# pc_sensything_v1_5.net
KiCad netlist of a schematic drawn in EAGLE
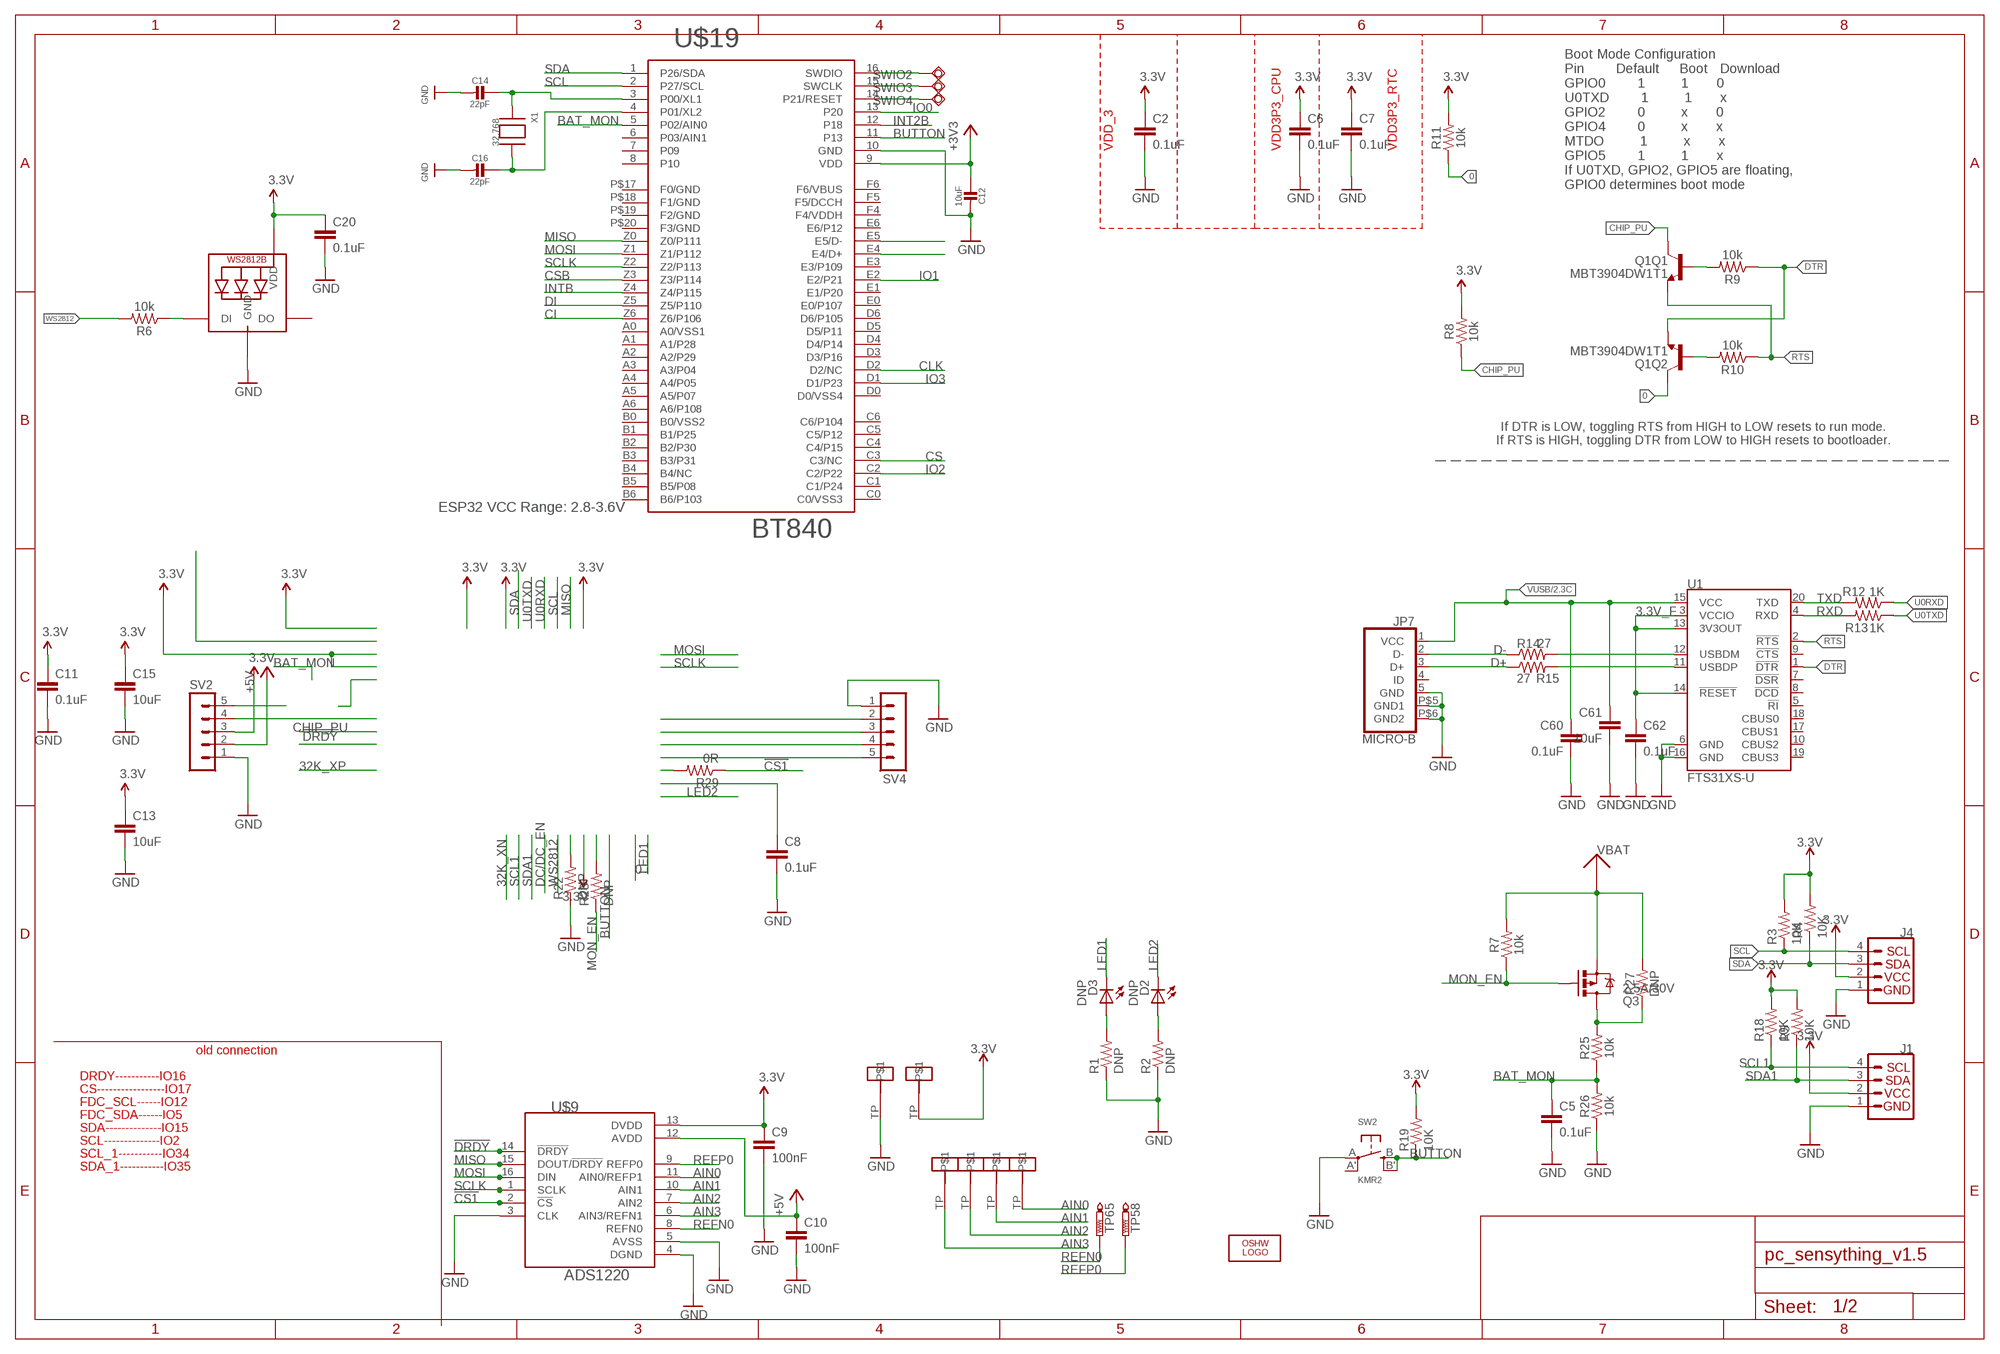
[diagram p0: schematic, sheet 1]
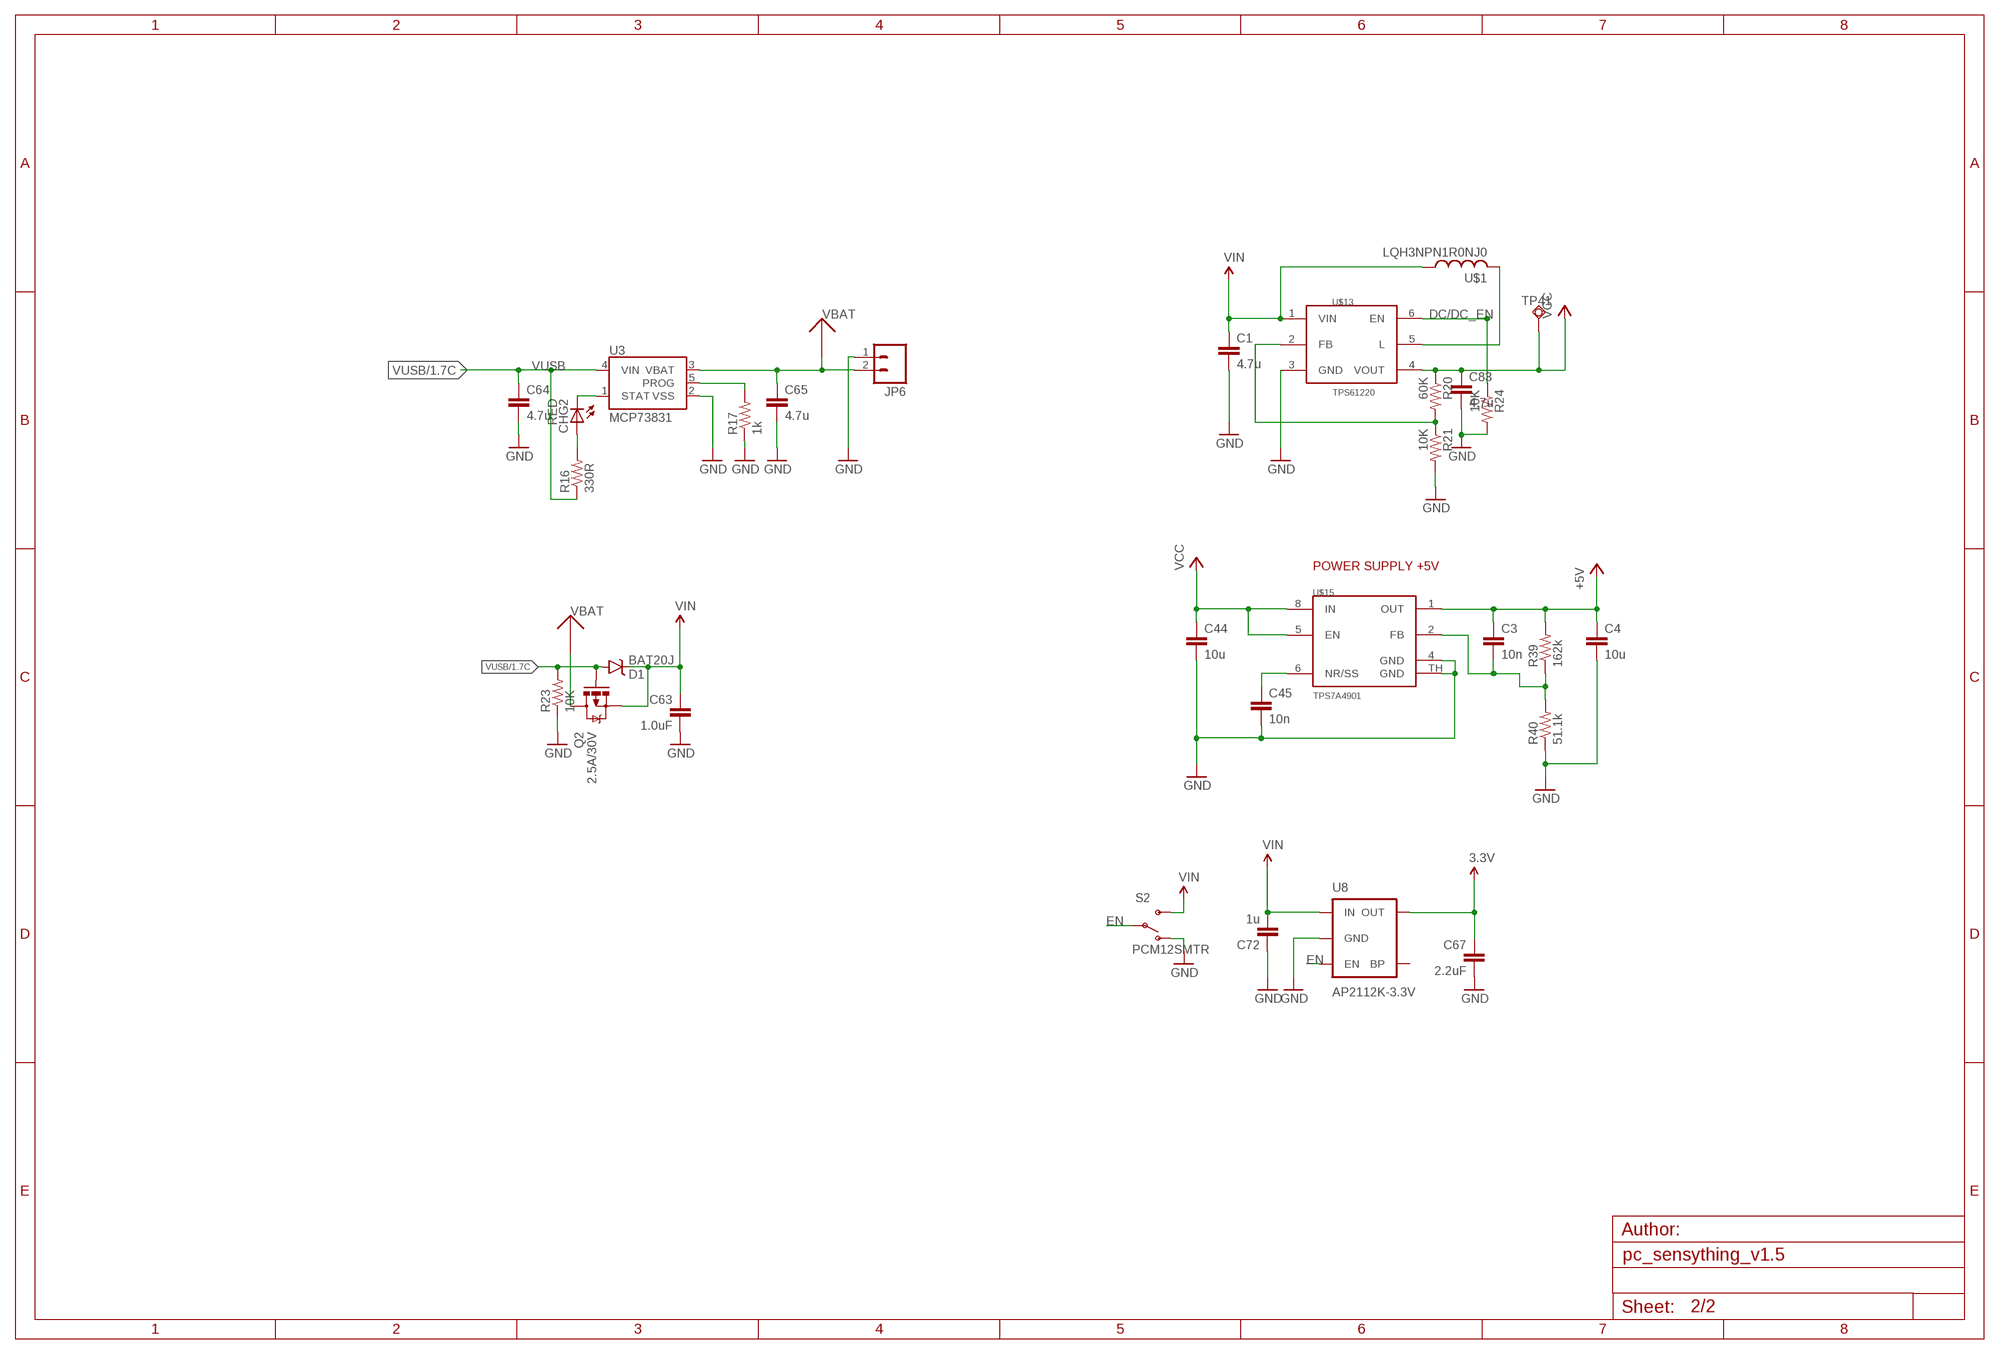
[diagram p1: schematic, sheet 2]

(export (version "E")
  (design (tool "Eeschema 10.0.6"))
  (components
    (comp (ref "C2")
      (value "0.1uF")
      (footprint "eagle-import:0402")
      (libsource (lib "eagle-import") (part "0.1UF-0402-16V-10%"))
    )
    (comp (ref "C5")
      (value "0.1uF")
      (footprint "eagle-import:0402")
      (libsource (lib "eagle-import") (part "0.1UF-0402-16V-10%"))
    )
    (comp (ref "C6")
      (value "0.1uF")
      (footprint "eagle-import:0402")
      (libsource (lib "eagle-import") (part "0.1UF-0402-16V-10%"))
    )
    (comp (ref "C7")
      (value "0.1uF")
      (footprint "eagle-import:0402")
      (libsource (lib "eagle-import") (part "0.1UF-0402-16V-10%"))
    )
    (comp (ref "C8")
      (value "0.1uF")
      (footprint "eagle-import:0402")
      (libsource (lib "eagle-import") (part "0.1UF-0402-16V-10%"))
    )
    (comp (ref "C9")
      (value "100nF")
      (footprint "eagle-import:C0805")
      (libsource (lib "eagle-import") (part "C-EUC0805"))
    )
    (comp (ref "C10")
      (value "100nF")
      (footprint "eagle-import:C0805")
      (libsource (lib "eagle-import") (part "C-EUC0805"))
    )
    (comp (ref "C11")
      (value "0.1uF")
      (footprint "eagle-import:0402")
      (libsource (lib "eagle-import") (part "0.1UF-0402-16V-10%"))
    )
    (comp (ref "C12")
      (value "10uF")
      (footprint "eagle-import:_0402")
      (libsource (lib "eagle-import") (part "CAP_CERAMIC_0402"))
    )
    (comp (ref "C13")
      (value "10uF")
      (footprint "eagle-import:0603")
      (libsource (lib "eagle-import") (part "10UF-0603-6.3V-20%"))
    )
    (comp (ref "C14")
      (value "22pF")
      (footprint "eagle-import:_0402")
      (libsource (lib "eagle-import") (part "CAP_CERAMIC_0402"))
    )
    (comp (ref "C15")
      (value "10uF")
      (footprint "eagle-import:0603")
      (libsource (lib "eagle-import") (part "10UF-0603-6.3V-20%"))
    )
    (comp (ref "C16")
      (value "22pF")
      (footprint "eagle-import:_0402")
      (libsource (lib "eagle-import") (part "CAP_CERAMIC_0402"))
    )
    (comp (ref "C20")
      (value "0.1uF")
      (footprint "eagle-import:0603")
      (libsource (lib "eagle-import") (part "0.1UF-0603-25V-(+80/-20%)"))
    )
    (comp (ref "C60")
      (value "0.1uF")
      (footprint "eagle-import:C0402")
      (libsource (lib "eagle-import") (part "C-EUC0402"))
    )
    (comp (ref "C61")
      (value "10uF")
      (footprint "eagle-import:C0805")
      (libsource (lib "eagle-import") (part "C-EUC0805"))
    )
    (comp (ref "C62")
      (value "0.1uF")
      (footprint "eagle-import:C0402")
      (libsource (lib "eagle-import") (part "C-EUC0402"))
    )
    (comp (ref "D2")
      (value "DNP")
      (footprint "eagle-import:CHIPLED_0603")
      (libsource (lib "eagle-import") (part "LEDCHIPLED_0603"))
    )
    (comp (ref "D3")
      (value "DNP")
      (footprint "eagle-import:CHIPLED_0603")
      (libsource (lib "eagle-import") (part "LEDCHIPLED_0603"))
    )
    (comp (ref "J1")
      (value "QWIIC_CONNECTORJS-1MM")
      (footprint "eagle-import:1X04_1MM_RA")
      (libsource (lib "eagle-import") (part "QWIIC_CONNECTORJS-1MM"))
    )
    (comp (ref "J4")
      (value "QWIIC_CONNECTORJS-1MM")
      (footprint "eagle-import:1X04_1MM_RA")
      (libsource (lib "eagle-import") (part "QWIIC_CONNECTORJS-1MM"))
    )
    (comp (ref "JP7")
      (value "MICRO-B")
      (footprint "eagle-import:MICRO-B")
      (libsource (lib "eagle-import") (part "MICRO-B"))
    )
    (comp (ref "LED1")
      (value "WS2812B5050")
      (footprint "eagle-import:WS2812B")
      (libsource (lib "eagle-import") (part "WS2812B5050"))
    )
    (comp (ref "LOGO3")
      (value "OSHW_LOGO_FILLX0200-NT")
      (footprint "eagle-import:OSHW_FILLX200_NOTEXT")
      (libsource (lib "eagle-import") (part "OSHW_LOGO_FILLX0200-NT"))
    )
    (comp (ref "Q1")
      (value "MBT3904DW1T1")
      (footprint "eagle-import:SC70-6")
      (libsource (lib "eagle-import") (part "MBT3904DW1T1"))
    )
    (comp (ref "Q3")
      (value "2.5A/30V")
      (footprint "eagle-import:SOT23-3")
      (libsource (lib "eagle-import") (part "MOSFET-PCHANNELDMG2307L"))
    )
    (comp (ref "R1")
      (value "DNP")
      (footprint "eagle-import:R0402")
      (libsource (lib "eagle-import") (part "R-US_R0402"))
    )
    (comp (ref "R2")
      (value "DNP")
      (footprint "eagle-import:R0402")
      (libsource (lib "eagle-import") (part "R-US_R0402"))
    )
    (comp (ref "R3")
      (value "10K")
      (footprint "eagle-import:R0402")
      (libsource (lib "eagle-import") (part "R-US_R0402"))
    )
    (comp (ref "R4")
      (value "10K")
      (footprint "eagle-import:R0402")
      (libsource (lib "eagle-import") (part "R-US_R0402"))
    )
    (comp (ref "R5")
      (value "10K")
      (footprint "eagle-import:R0402")
      (libsource (lib "eagle-import") (part "R-US_R0402"))
    )
    (comp (ref "R6")
      (value "10k")
      (footprint "eagle-import:0603")
      (libsource (lib "eagle-import") (part "10KOHM-1/10W-1%(0603)0603"))
    )
    (comp (ref "R7")
      (value "10k")
      (footprint "eagle-import:0603")
      (libsource (lib "eagle-import") (part "10KOHM-1/10W-1%(0603)0603"))
    )
    (comp (ref "R8")
      (value "10k")
      (footprint "eagle-import:0603")
      (libsource (lib "eagle-import") (part "10KOHM-1/10W-1%(0603)0603"))
    )
    (comp (ref "R9")
      (value "10k")
      (footprint "eagle-import:0603")
      (libsource (lib "eagle-import") (part "10KOHM-0603-1/10W-1%"))
    )
    (comp (ref "R10")
      (value "10k")
      (footprint "eagle-import:0603")
      (libsource (lib "eagle-import") (part "10KOHM-0603-1/10W-1%"))
    )
    (comp (ref "R11")
      (value "10k")
      (footprint "eagle-import:0603")
      (libsource (lib "eagle-import") (part "10KOHM-1/10W-1%(0603)0603"))
    )
    (comp (ref "R12")
      (value "1K")
      (footprint "eagle-import:R0402")
      (libsource (lib "eagle-import") (part "R-US_R0402"))
    )
    (comp (ref "R13")
      (value "1K")
      (footprint "eagle-import:R0402")
      (libsource (lib "eagle-import") (part "R-US_R0402"))
    )
    (comp (ref "R14")
      (value "27")
      (footprint "eagle-import:R0402")
      (libsource (lib "eagle-import") (part "R-US_R0402"))
    )
    (comp (ref "R15")
      (value "27")
      (footprint "eagle-import:R0402")
      (libsource (lib "eagle-import") (part "R-US_R0402"))
    )
    (comp (ref "R18")
      (value "10K")
      (footprint "eagle-import:R0402")
      (libsource (lib "eagle-import") (part "R-US_R0402"))
    )
    (comp (ref "R19")
      (value "10K")
      (footprint "eagle-import:R0402")
      (libsource (lib "eagle-import") (part "R-US_R0402"))
    )
    (comp (ref "R22")
      (value "DNP")
      (footprint "eagle-import:R0402")
      (libsource (lib "eagle-import") (part "R-US_R0402"))
    )
    (comp (ref "R25")
      (value "10k")
      (footprint "eagle-import:0603")
      (libsource (lib "eagle-import") (part "10KOHM-1/10W-1%(0603)0603"))
    )
    (comp (ref "R26")
      (value "10k")
      (footprint "eagle-import:0603")
      (libsource (lib "eagle-import") (part "10KOHM-1/10W-1%(0603)0603"))
    )
    (comp (ref "R27")
      (value "DNP")
      (footprint "eagle-import:0603")
      (libsource (lib "eagle-import") (part "10KOHM-1/10W-1%(0603)0603"))
    )
    (comp (ref "R28")
      (value "DNP")
      (footprint "eagle-import:R0402")
      (libsource (lib "eagle-import") (part "R-US_R0402"))
    )
    (comp (ref "R29")
      (value "0R")
      (footprint "eagle-import:R0402")
      (libsource (lib "eagle-import") (part "R-US_R0402"))
    )
    (comp (ref "SV2")
      (value "MA05-1")
      (footprint "eagle-import:MA05-1")
      (libsource (lib "eagle-import") (part "MA05-1"))
    )
    (comp (ref "SV4")
      (value "MA05-1")
      (footprint "eagle-import:MA05-1")
      (libsource (lib "eagle-import") (part "MA05-1"))
    )
    (comp (ref "SW2")
      (value "KMR2")
      (footprint "eagle-import:BTN_KMR2_4.6X2.8")
      (libsource (lib "eagle-import") (part "SWITCH_TACT_SMT4.6X2.8"))
    )
    (comp (ref "SWIO2")
      (value "TPSQTP11R")
      (footprint "eagle-import:TP11R")
      (libsource (lib "eagle-import") (part "TPSQTP11R"))
    )
    (comp (ref "SWIO3")
      (value "TPSQTP11R")
      (footprint "eagle-import:TP11R")
      (libsource (lib "eagle-import") (part "TPSQTP11R"))
    )
    (comp (ref "SWIO4")
      (value "TPSQTP11R")
      (footprint "eagle-import:TP11R")
      (libsource (lib "eagle-import") (part "TPSQTP11R"))
    )
    (comp (ref "TP58")
      (value "PTR1PAD1-13")
      (footprint "eagle-import:P1-13")
      (libsource (lib "eagle-import") (part "PTR1PAD1-13"))
    )
    (comp (ref "TP65")
      (value "PTR1PAD1-13")
      (footprint "eagle-import:P1-13")
      (libsource (lib "eagle-import") (part "PTR1PAD1-13"))
    )
    (comp (ref "U$3")
      (value "SENSYTHING_CON")
      (footprint "eagle-import:SENSYTHING_CON")
      (libsource (lib "eagle-import") (part "SENSYTHING_CON"))
    )
    (comp (ref "U$7")
      (value "SENSYTHING_CON")
      (footprint "eagle-import:SENSYTHING_CON")
      (libsource (lib "eagle-import") (part "SENSYTHING_CON"))
    )
    (comp (ref "U$8")
      (value "SENSYTHING_CON")
      (footprint "eagle-import:SENSYTHING_CON")
      (libsource (lib "eagle-import") (part "SENSYTHING_CON"))
    )
    (comp (ref "U$9")
      (value "ADS1220")
      (footprint "eagle-import:TSSOP-16")
      (libsource (lib "eagle-import") (part "ADS1220"))
    )
    (comp (ref "U$11")
      (value "SENSYTHING_CON")
      (footprint "eagle-import:SENSYTHING_CON")
      (libsource (lib "eagle-import") (part "SENSYTHING_CON"))
    )
    (comp (ref "U$12")
      (value "SENSYTHING_CON")
      (footprint "eagle-import:SENSYTHING_CON")
      (libsource (lib "eagle-import") (part "SENSYTHING_CON"))
    )
    (comp (ref "U$14")
      (value "SENSYTHING_CON")
      (footprint "eagle-import:SENSYTHING_CON")
      (libsource (lib "eagle-import") (part "SENSYTHING_CON"))
    )
    (comp (ref "U$19")
      (value "BT840")
      (footprint "eagle-import:BT840")
      (libsource (lib "eagle-import") (part "BT840"))
    )
    (comp (ref "U1")
      (value "FTS31XS-U")
      (footprint "eagle-import:SSOP20_L")
      (libsource (lib "eagle-import") (part "FT231XS"))
    )
    (comp (ref "X1")
      (value "32.768")
      (footprint "eagle-import:XTAL3215")
      (libsource (lib "eagle-import") (part "XTAL-3.2X1.5"))
    )
    (comp (ref "C1")
      (value "4.7u")
      (footprint "eagle-import:C0805")
      (libsource (lib "eagle-import") (part "C-EUC0805"))
    )
    (comp (ref "C3")
      (value "10n")
      (footprint "eagle-import:C0402")
      (libsource (lib "eagle-import") (part "C-EUC0402"))
    )
    (comp (ref "C4")
      (value "10u")
      (footprint "eagle-import:C0805")
      (libsource (lib "eagle-import") (part "C-EUC0805"))
    )
    (comp (ref "C44")
      (value "10u")
      (footprint "eagle-import:C0805")
      (libsource (lib "eagle-import") (part "C-EUC0805"))
    )
    (comp (ref "C45")
      (value "10n")
      (footprint "eagle-import:C0402")
      (libsource (lib "eagle-import") (part "C-EUC0402"))
    )
    (comp (ref "C63")
      (value "1.0uF")
      (footprint "eagle-import:C0402")
      (libsource (lib "eagle-import") (part "C-EUC0402"))
    )
    (comp (ref "C64")
      (value "4.7u")
      (footprint "eagle-import:C0805")
      (libsource (lib "eagle-import") (part "C-EUC0805"))
    )
    (comp (ref "C65")
      (value "4.7u")
      (footprint "eagle-import:C0805")
      (libsource (lib "eagle-import") (part "C-EUC0805"))
    )
    (comp (ref "C67")
      (value "2.2uF")
      (footprint "eagle-import:C0402")
      (libsource (lib "eagle-import") (part "C-EUC0402"))
    )
    (comp (ref "C72")
      (value "1u")
      (footprint "eagle-import:C0402")
      (libsource (lib "eagle-import") (part "C-EUC0402"))
    )
    (comp (ref "C83")
      (value "4.7u")
      (footprint "eagle-import:C0805")
      (libsource (lib "eagle-import") (part "C-EUC0805"))
    )
    (comp (ref "CHG2")
      (value "RED")
      (footprint "eagle-import:CHIPLED_0603")
      (libsource (lib "eagle-import") (part "LEDCHIPLED_0603"))
    )
    (comp (ref "D1")
      (value "BAT20J")
      (footprint "eagle-import:SOD-323")
      (libsource (lib "eagle-import") (part "DIODE-SCHOTTKY-BAT20J"))
    )
    (comp (ref "JP6")
      (value "M02-JST-2MM-SMT")
      (footprint "eagle-import:JST-2-SMD")
      (libsource (lib "eagle-import") (part "M02-JST-2MM-SMT"))
    )
    (comp (ref "Q2")
      (value "2.5A/30V")
      (footprint "eagle-import:SOT23-3")
      (libsource (lib "eagle-import") (part "MOSFET-PCHANNELDMG2307L"))
    )
    (comp (ref "R16")
      (value "330R")
      (footprint "eagle-import:R0402")
      (libsource (lib "eagle-import") (part "R-US_R0402"))
    )
    (comp (ref "R17")
      (value "1k")
      (footprint "eagle-import:R0402")
      (libsource (lib "eagle-import") (part "R-US_R0402"))
    )
    (comp (ref "R20")
      (value "60K")
      (footprint "eagle-import:R0805")
      (libsource (lib "eagle-import") (part "R-US_R0805"))
    )
    (comp (ref "R21")
      (value "10K")
      (footprint "eagle-import:R0805")
      (libsource (lib "eagle-import") (part "R-US_R0805"))
    )
    (comp (ref "R23")
      (value "10K")
      (footprint "eagle-import:R0402")
      (libsource (lib "eagle-import") (part "R-US_R0402"))
    )
    (comp (ref "R24")
      (value "10K")
      (footprint "eagle-import:R0402")
      (libsource (lib "eagle-import") (part "R-US_R0402"))
    )
    (comp (ref "R39")
      (value "162k")
      (footprint "eagle-import:R0805")
      (libsource (lib "eagle-import") (part "R-US_R0805"))
    )
    (comp (ref "R40")
      (value "51.1k")
      (footprint "eagle-import:R0805")
      (libsource (lib "eagle-import") (part "R-US_R0805"))
    )
    (comp (ref "S2")
      (value "PCM12SMTR")
      (footprint "eagle-import:SWITCH-SPST-SMD-A")
      (libsource (lib "eagle-import") (part "SWITCH-SPDT-SMD-A"))
    )
    (comp (ref "TP41")
      (value "TPSQB1,27")
      (footprint "eagle-import:B1,27")
      (libsource (lib "eagle-import") (part "TPSQB1,27"))
    )
    (comp (ref "U$1")
      (value "LQH3NPN1R0NJ0")
      (footprint "eagle-import:LQH3NP")
      (libsource (lib "eagle-import") (part "LQH3NPN1R0NJ0"))
    )
    (comp (ref "U$13")
      (value "TPS61220")
      (footprint "eagle-import:SC-70-6")
      (libsource (lib "eagle-import") (part "TPS61222"))
    )
    (comp (ref "U$15")
      (value "TPS7A4901")
      (footprint "eagle-import:S-PDSO-G08")
      (libsource (lib "eagle-import") (part "TPS7A4901"))
    )
    (comp (ref "U3")
      (value "MCP73831")
      (footprint "eagle-import:SOT23-5")
      (libsource (lib "eagle-import") (part "MCP73831"))
    )
    (comp (ref "U8")
      (value "AP2112K-3.3V")
      (footprint "eagle-import:SOT23-5")
      (libsource (lib "eagle-import") (part "V_REG_LDOSMD"))
    )
  )
  (nets
    (net (code "1") (name "+3V3") (class "Default")
      (node (ref "C12") (pin "1") (pinfunction "1_1") (pintype "passive"))
      (node (ref "U$19") (pin "9") (pinfunction "VDD_9") (pintype "bidirectional"))
    )
    (net (code "2") (name "+5V") (class "Default")
      (node (ref "C10") (pin "1") (pinfunction "1_1") (pintype "passive"))
      (node (ref "C3") (pin "1") (pinfunction "1_1") (pintype "passive"))
      (node (ref "C4") (pin "1") (pinfunction "1_1") (pintype "passive"))
      (node (ref "R39") (pin "2") (pinfunction "2_2") (pintype "passive"))
      (node (ref "SV2") (pin "2") (pinfunction "2_2") (pintype "passive"))
      (node (ref "U$15") (pin "1") (pinfunction "OUT_1") (pintype "bidirectional"))
      (node (ref "U$9") (pin "12") (pinfunction "AVDD_12") (pintype "bidirectional"))
    )
    (net (code "3") (name "0") (class "Default")
      (node (ref "Q1") (pin "6") (pinfunction "C_6") (pintype "passive"))
      (node (ref "R11") (pin "1") (pinfunction "1_1") (pintype "passive"))
    )
    (net (code "4") (name "3.3V") (class "Default")
      (node (ref "C11") (pin "1") (pinfunction "1_1") (pintype "passive"))
      (node (ref "C13") (pin "1") (pinfunction "1_1") (pintype "passive"))
      (node (ref "C15") (pin "1") (pinfunction "1_1") (pintype "passive"))
      (node (ref "C2") (pin "1") (pinfunction "1_1") (pintype "passive"))
      (node (ref "C20") (pin "1") (pinfunction "1_1") (pintype "passive"))
      (node (ref "C6") (pin "1") (pinfunction "1_1") (pintype "passive"))
      (node (ref "C67") (pin "1") (pinfunction "1_1") (pintype "passive"))
      (node (ref "C7") (pin "1") (pinfunction "1_1") (pintype "passive"))
      (node (ref "C9") (pin "1") (pinfunction "1_1") (pintype "passive"))
      (node (ref "J1") (pin "2") (pinfunction "2_2") (pintype "power_in"))
      (node (ref "J4") (pin "2") (pinfunction "2_2") (pintype "power_in"))
      (node (ref "LED1") (pin "1-VDD") (pinfunction "VDD_1-VDD") (pintype "power_in"))
      (node (ref "R11") (pin "2") (pinfunction "2_2") (pintype "passive"))
      (node (ref "R18") (pin "2") (pinfunction "2_2") (pintype "passive"))
      (node (ref "R19") (pin "2") (pinfunction "2_2") (pintype "passive"))
      (node (ref "R3") (pin "2") (pinfunction "2_2") (pintype "passive"))
      (node (ref "R4") (pin "2") (pinfunction "2_2") (pintype "passive"))
      (node (ref "R5") (pin "2") (pinfunction "2_2") (pintype "passive"))
      (node (ref "R8") (pin "2") (pinfunction "2_2") (pintype "passive"))
      (node (ref "SV2") (pin "3") (pinfunction "3_3") (pintype "passive"))
      (node (ref "U$14") (pin "TP") (pinfunction "P$1_TP") (pintype "bidirectional"))
      (node (ref "U$9") (pin "13") (pinfunction "DVDD_13") (pintype "bidirectional"))
      (node (ref "U8") (pin "5") (pinfunction "OUT_5") (pintype "passive"))
    )
    (net (code "5") (name "3.3V_F") (class "Default")
      (node (ref "C62") (pin "1") (pinfunction "1_1") (pintype "passive"))
      (node (ref "U1") (pin "13") (pinfunction "3V3OUT_13") (pintype "bidirectional"))
      (node (ref "U1") (pin "14") (pinfunction "~{RESET}_14") (pintype "bidirectional"))
      (node (ref "U1") (pin "3") (pinfunction "VCCIO_3") (pintype "bidirectional"))
    )
    (net (code "8") (name "AIN0") (class "Default")
      (node (ref "U$11") (pin "TP") (pinfunction "P$1_TP") (pintype "bidirectional"))
      (node (ref "U$9") (pin "11") (pinfunction "AIN0/REFP1_11") (pintype "bidirectional"))
    )
    (net (code "9") (name "AIN1") (class "Default")
      (node (ref "U$8") (pin "TP") (pinfunction "P$1_TP") (pintype "bidirectional"))
      (node (ref "U$9") (pin "10") (pinfunction "AIN1_10") (pintype "bidirectional"))
    )
    (net (code "10") (name "AIN2") (class "Default")
      (node (ref "U$7") (pin "TP") (pinfunction "P$1_TP") (pintype "bidirectional"))
      (node (ref "U$9") (pin "7") (pinfunction "AIN2_7") (pintype "bidirectional"))
    )
    (net (code "11") (name "AIN3") (class "Default")
      (node (ref "U$3") (pin "TP") (pinfunction "P$1_TP") (pintype "bidirectional"))
      (node (ref "U$9") (pin "6") (pinfunction "AIN3/REFN1_6") (pintype "bidirectional"))
    )
    (net (code "12") (name "BAT_MON") (class "Default")
      (node (ref "C5") (pin "1") (pinfunction "1_1") (pintype "passive"))
      (node (ref "R25") (pin "1") (pinfunction "1_1") (pintype "passive"))
      (node (ref "R26") (pin "2") (pinfunction "2_2") (pintype "passive"))
      (node (ref "U$19") (pin "5") (pinfunction "P02/AIN0_5") (pintype "bidirectional"))
    )
    (net (code "13") (name "BUTTON") (class "Default")
      (node (ref "R19") (pin "1") (pinfunction "1_1") (pintype "passive"))
      (node (ref "SW2") (pin "B") (pinfunction "S_B") (pintype "passive"))
      (node (ref "SW2") (pin "B'") (pinfunction "S1_B'") (pintype "passive"))
      (node (ref "U$19") (pin "11") (pinfunction "P13_11") (pintype "bidirectional"))
    )
    (net (code "14") (name "CHIP_PU") (class "Default")
      (node (ref "Q1") (pin "3") (pinfunction "C_3") (pintype "passive"))
      (node (ref "R8") (pin "1") (pinfunction "1_1") (pintype "passive"))
    )
    (net (code "15") (name "CI") (class "Default")
      (node (ref "U$19") (pin "Z6") (pinfunction "Z6/P106_Z6") (pintype "bidirectional"))
    )
    (net (code "16") (name "CLK") (class "Default")
      (node (ref "U$19") (pin "D2") (pinfunction "D2/NC_D2") (pintype "bidirectional"))
    )
    (net (code "17") (name "CS") (class "Default")
      (node (ref "U$19") (pin "C3") (pinfunction "C3/NC_C3") (pintype "bidirectional"))
    )
    (net (code "18") (name "CSB") (class "Default")
      (node (ref "U$19") (pin "Z3") (pinfunction "Z3/P114_Z3") (pintype "bidirectional"))
    )
    (net (code "19") (name "D+") (class "Default")
      (node (ref "JP7") (pin "3") (pinfunction "D+_3") (pintype "bidirectional"))
      (node (ref "R15") (pin "1") (pinfunction "1_1") (pintype "passive"))
    )
    (net (code "20") (name "D-") (class "Default")
      (node (ref "JP7") (pin "2") (pinfunction "D-_2") (pintype "bidirectional"))
      (node (ref "R14") (pin "1") (pinfunction "1_1") (pintype "passive"))
    )
    (net (code "21") (name "DC{slash}DC_EN") (class "Default")
      (node (ref "R24") (pin "1") (pinfunction "1_1") (pintype "passive"))
      (node (ref "U$13") (pin "6") (pinfunction "EN_6") (pintype "bidirectional"))
    )
    (net (code "22") (name "DI") (class "Default")
      (node (ref "U$19") (pin "Z5") (pinfunction "Z5/P110_Z5") (pintype "bidirectional"))
    )
    (net (code "23") (name "DTR") (class "Default")
      (node (ref "Q1") (pin "1") (pinfunction "E_1") (pintype "passive"))
      (node (ref "R9") (pin "1") (pinfunction "1_1") (pintype "passive"))
      (node (ref "U1") (pin "1") (pinfunction "~{DTR}_1") (pintype "bidirectional"))
    )
    (net (code "24") (name "EN") (class "Default")
      (node (ref "S2") (pin "2") (pinfunction "P_2") (pintype "passive"))
      (node (ref "U8") (pin "3") (pinfunction "EN_3") (pintype "input"))
    )
    (net (code "25") (name "GND") (class "Default")
      (node (ref "C1") (pin "2") (pinfunction "2_2") (pintype "passive"))
      (node (ref "C10") (pin "2") (pinfunction "2_2") (pintype "passive"))
      (node (ref "C11") (pin "2") (pinfunction "2_2") (pintype "passive"))
      (node (ref "C12") (pin "2") (pinfunction "2_2") (pintype "passive"))
      (node (ref "C13") (pin "2") (pinfunction "2_2") (pintype "passive"))
      (node (ref "C14") (pin "2") (pinfunction "2_2") (pintype "passive"))
      (node (ref "C15") (pin "2") (pinfunction "2_2") (pintype "passive"))
      (node (ref "C16") (pin "2") (pinfunction "2_2") (pintype "passive"))
      (node (ref "C2") (pin "2") (pinfunction "2_2") (pintype "passive"))
      (node (ref "C20") (pin "2") (pinfunction "2_2") (pintype "passive"))
      (node (ref "C4") (pin "2") (pinfunction "2_2") (pintype "passive"))
      (node (ref "C44") (pin "2") (pinfunction "2_2") (pintype "passive"))
      (node (ref "C45") (pin "2") (pinfunction "2_2") (pintype "passive"))
      (node (ref "C5") (pin "2") (pinfunction "2_2") (pintype "passive"))
      (node (ref "C6") (pin "2") (pinfunction "2_2") (pintype "passive"))
      (node (ref "C60") (pin "2") (pinfunction "2_2") (pintype "passive"))
      (node (ref "C61") (pin "2") (pinfunction "2_2") (pintype "passive"))
      (node (ref "C62") (pin "2") (pinfunction "2_2") (pintype "passive"))
      (node (ref "C63") (pin "2") (pinfunction "2_2") (pintype "passive"))
      (node (ref "C64") (pin "2") (pinfunction "2_2") (pintype "passive"))
      (node (ref "C65") (pin "2") (pinfunction "2_2") (pintype "passive"))
      (node (ref "C67") (pin "2") (pinfunction "2_2") (pintype "passive"))
      (node (ref "C7") (pin "2") (pinfunction "2_2") (pintype "passive"))
      (node (ref "C72") (pin "1") (pinfunction "1_1") (pintype "passive"))
      (node (ref "C8") (pin "2") (pinfunction "2_2") (pintype "passive"))
      (node (ref "C83") (pin "2") (pinfunction "2_2") (pintype "passive"))
      (node (ref "C9") (pin "2") (pinfunction "2_2") (pintype "passive"))
      (node (ref "J1") (pin "1") (pinfunction "1_1") (pintype "power_in"))
      (node (ref "J4") (pin "1") (pinfunction "1_1") (pintype "power_in"))
      (node (ref "JP6") (pin "1") (pinfunction "1_1") (pintype "passive"))
      (node (ref "JP7") (pin "5") (pinfunction "GND_5") (pintype "bidirectional"))
      (node (ref "JP7") (pin "P$5") (pinfunction "GND1_P$5") (pintype "bidirectional"))
      (node (ref "JP7") (pin "P$6") (pinfunction "GND2_P$6") (pintype "bidirectional"))
      (node (ref "LED1") (pin "3-GND") (pinfunction "GND_3-GND") (pintype "power_in"))
      (node (ref "R1") (pin "1") (pinfunction "1_1") (pintype "passive"))
      (node (ref "R17") (pin "1") (pinfunction "1_1") (pintype "passive"))
      (node (ref "R2") (pin "1") (pinfunction "1_1") (pintype "passive"))
      (node (ref "R21") (pin "2") (pinfunction "2_2") (pintype "passive"))
      (node (ref "R22") (pin "1") (pinfunction "1_1") (pintype "passive"))
      (node (ref "R23") (pin "1") (pinfunction "1_1") (pintype "passive"))
      (node (ref "R24") (pin "2") (pinfunction "2_2") (pintype "passive"))
      (node (ref "R26") (pin "1") (pinfunction "1_1") (pintype "passive"))
      (node (ref "R40") (pin "1") (pinfunction "1_1") (pintype "passive"))
      (node (ref "S2") (pin "1") (pinfunction "O_1") (pintype "passive"))
      (node (ref "SV2") (pin "1") (pinfunction "1_1") (pintype "passive"))
      (node (ref "SV4") (pin "1") (pinfunction "1_1") (pintype "passive"))
      (node (ref "SW2") (pin "A") (pinfunction "P_A") (pintype "passive"))
      (node (ref "U$12") (pin "TP") (pinfunction "P$1_TP") (pintype "bidirectional"))
      (node (ref "U$13") (pin "3") (pinfunction "GND_3") (pintype "bidirectional"))
      (node (ref "U$15") (pin "4") (pinfunction "GND_4") (pintype "bidirectional"))
      (node (ref "U$15") (pin "TH") (pinfunction "GND_TH") (pintype "bidirectional"))
      (node (ref "U$19") (pin "10") (pinfunction "GND_10") (pintype "bidirectional"))
      (node (ref "U$9") (pin "3") (pinfunction "CLK_3") (pintype "bidirectional"))
      (node (ref "U$9") (pin "4") (pinfunction "DGND_4") (pintype "bidirectional"))
      (node (ref "U$9") (pin "5") (pinfunction "AVSS_5") (pintype "bidirectional"))
      (node (ref "U1") (pin "16") (pinfunction "GND_16") (pintype "bidirectional"))
      (node (ref "U1") (pin "6") (pinfunction "GND_6") (pintype "bidirectional"))
      (node (ref "U3") (pin "2") (pinfunction "VSS_2") (pintype "power_in"))
      (node (ref "U8") (pin "2") (pinfunction "GND_2") (pintype "input"))
    )
    (net (code "26") (name "INT2B") (class "Default")
      (node (ref "U$19") (pin "12") (pinfunction "P18_12") (pintype "bidirectional"))
    )
    (net (code "27") (name "INTB") (class "Default")
      (node (ref "U$19") (pin "Z4") (pinfunction "Z4/P115_Z4") (pintype "bidirectional"))
    )
    (net (code "28") (name "IO0") (class "Default")
      (node (ref "U$19") (pin "13") (pinfunction "P20_13") (pintype "bidirectional"))
    )
    (net (code "29") (name "IO1") (class "Default")
      (node (ref "U$19") (pin "E2") (pinfunction "E2/P21_E2") (pintype "bidirectional"))
    )
    (net (code "30") (name "IO2") (class "Default")
      (node (ref "U$19") (pin "C2") (pinfunction "C2/P22_C2") (pintype "bidirectional"))
    )
    (net (code "31") (name "IO3") (class "Default")
      (node (ref "U$19") (pin "D1") (pinfunction "D1/P23_D1") (pintype "bidirectional"))
    )
    (net (code "32") (name "LED1") (class "Default")
      (node (ref "D3") (pin "C") (pinfunction "C_C") (pintype "passive"))
    )
    (net (code "33") (name "LED2") (class "Default")
      (node (ref "D2") (pin "C") (pinfunction "C_C") (pintype "passive"))
    )
    (net (code "34") (name "MISO") (class "Default")
      (node (ref "U$19") (pin "Z0") (pinfunction "Z0/P111_Z0") (pintype "bidirectional"))
      (node (ref "U$9") (pin "15") (pinfunction "DOUT/~{DRDY}_15") (pintype "bidirectional"))
    )
    (net (code "35") (name "MON_EN") (class "Default")
      (node (ref "Q3") (pin "1") (pinfunction "G_1") (pintype "passive"))
      (node (ref "R28") (pin "1") (pinfunction "1_1") (pintype "passive"))
      (node (ref "R7") (pin "1") (pinfunction "1_1") (pintype "passive"))
    )
    (net (code "36") (name "MOSI") (class "Default")
      (node (ref "U$19") (pin "Z1") (pinfunction "Z1/P112_Z1") (pintype "bidirectional"))
      (node (ref "U$9") (pin "16") (pinfunction "DIN_16") (pintype "bidirectional"))
    )
    (net (code "37") (name "Net-(CHG2-PadA)") (class "Default")
      (node (ref "CHG2") (pin "A") (pinfunction "A_A") (pintype "passive"))
      (node (ref "R16") (pin "2") (pinfunction "2_2") (pintype "passive"))
    )
    (net (code "38") (name "Net-(D2-PadA)") (class "Default")
      (node (ref "D2") (pin "A") (pinfunction "A_A") (pintype "passive"))
      (node (ref "R2") (pin "2") (pinfunction "2_2") (pintype "passive"))
    )
    (net (code "39") (name "Net-(D3-PadA)") (class "Default")
      (node (ref "D3") (pin "A") (pinfunction "A_A") (pintype "passive"))
      (node (ref "R1") (pin "2") (pinfunction "2_2") (pintype "passive"))
    )
    (net (code "40") (name "Net-(LED1-DI)") (class "Default")
      (node (ref "LED1") (pin "4-DIN") (pinfunction "DI_4-DIN") (pintype "input"))
      (node (ref "R6") (pin "1") (pinfunction "1_1") (pintype "passive"))
    )
    (net (code "41") (name "Net-(Q1A-B)") (class "Default")
      (node (ref "Q1") (pin "5") (pinfunction "B_5") (pintype "passive"))
      (node (ref "R9") (pin "2") (pinfunction "2_2") (pintype "passive"))
    )
    (net (code "42") (name "Net-(Q1B-B)") (class "Default")
      (node (ref "Q1") (pin "2") (pinfunction "B_2") (pintype "passive"))
      (node (ref "R10") (pin "2") (pinfunction "2_2") (pintype "passive"))
    )
    (net (code "43") (name "Net-(Q3-D)") (class "Default")
      (node (ref "Q3") (pin "3") (pinfunction "D_3") (pintype "passive"))
      (node (ref "R25") (pin "2") (pinfunction "2_2") (pintype "passive"))
      (node (ref "R27") (pin "1") (pinfunction "1_1") (pintype "passive"))
    )
    (net (code "44") (name "Net-(U$1-2)") (class "Default")
      (node (ref "U$1") (pin "P$2") (pinfunction "2_P$2") (pintype "passive"))
      (node (ref "U$13") (pin "5") (pinfunction "L_5") (pintype "bidirectional"))
    )
    (net (code "45") (name "Net-(U$13-FB)") (class "Default")
      (node (ref "R20") (pin "2") (pinfunction "2_2") (pintype "passive"))
      (node (ref "R21") (pin "1") (pinfunction "1_1") (pintype "passive"))
      (node (ref "U$13") (pin "2") (pinfunction "FB_2") (pintype "bidirectional"))
    )
    (net (code "46") (name "Net-(U$15-FB)") (class "Default")
      (node (ref "C3") (pin "2") (pinfunction "2_2") (pintype "passive"))
      (node (ref "R39") (pin "1") (pinfunction "1_1") (pintype "passive"))
      (node (ref "R40") (pin "2") (pinfunction "2_2") (pintype "passive"))
      (node (ref "U$15") (pin "2") (pinfunction "FB_2") (pintype "bidirectional"))
    )
    (net (code "47") (name "Net-(U$15-NR{slash}SS)") (class "Default")
      (node (ref "C45") (pin "1") (pinfunction "1_1") (pintype "passive"))
      (node (ref "U$15") (pin "6") (pinfunction "NR/SS_6") (pintype "bidirectional"))
    )
    (net (code "48") (name "Net-(U$19-P00{slash}XL1)") (class "Default")
      (node (ref "C14") (pin "1") (pinfunction "1_1") (pintype "passive"))
      (node (ref "U$19") (pin "3") (pinfunction "P00/XL1_3") (pintype "bidirectional"))
      (node (ref "X1") (pin "P$1") (pinfunction "P$1_P$1") (pintype "bidirectional"))
    )
    (net (code "49") (name "Net-(U$19-P01{slash}XL2)") (class "Default")
      (node (ref "C16") (pin "1") (pinfunction "1_1") (pintype "passive"))
      (node (ref "U$19") (pin "4") (pinfunction "P01/XL2_4") (pintype "bidirectional"))
      (node (ref "X1") (pin "P$2") (pinfunction "P$2_P$2") (pintype "bidirectional"))
    )
    (net (code "50") (name "Net-(U$19-P21{slash}RESET)") (class "Default")
      (node (ref "SWIO4") (pin "TP") (pinfunction "TP_TP") (pintype "input"))
      (node (ref "U$19") (pin "14") (pinfunction "P21/RESET_14") (pintype "bidirectional"))
    )
    (net (code "51") (name "Net-(U$19-SWCLK)") (class "Default")
      (node (ref "SWIO3") (pin "TP") (pinfunction "TP_TP") (pintype "input"))
      (node (ref "U$19") (pin "15") (pinfunction "SWCLK_15") (pintype "bidirectional"))
    )
    (net (code "52") (name "Net-(U$19-SWDIO)") (class "Default")
      (node (ref "SWIO2") (pin "TP") (pinfunction "TP_TP") (pintype "input"))
      (node (ref "U$19") (pin "16") (pinfunction "SWDIO_16") (pintype "bidirectional"))
    )
    (net (code "53") (name "Net-(U1-USBDM)") (class "Default")
      (node (ref "R14") (pin "2") (pinfunction "2_2") (pintype "passive"))
      (node (ref "U1") (pin "12") (pinfunction "USBDM_12") (pintype "bidirectional"))
    )
    (net (code "54") (name "Net-(U1-USBDP)") (class "Default")
      (node (ref "R15") (pin "2") (pinfunction "2_2") (pintype "passive"))
      (node (ref "U1") (pin "11") (pinfunction "USBDP_11") (pintype "bidirectional"))
    )
    (net (code "55") (name "Net-(U3-PROG)") (class "Default")
      (node (ref "R17") (pin "2") (pinfunction "2_2") (pintype "passive"))
      (node (ref "U3") (pin "5") (pinfunction "PROG_5") (pintype "input"))
    )
    (net (code "56") (name "Net-(U3-STAT)") (class "Default")
      (node (ref "CHG2") (pin "C") (pinfunction "C_C") (pintype "passive"))
      (node (ref "U3") (pin "1") (pinfunction "STAT_1") (pintype "output"))
    )
    (net (code "57") (name "REFN0") (class "Default")
      (node (ref "TP65") (pin "TP") (pinfunction "TP_TP") (pintype "input"))
      (node (ref "U$9") (pin "8") (pinfunction "REFN0_8") (pintype "bidirectional"))
    )
    (net (code "58") (name "REFP0") (class "Default")
      (node (ref "TP58") (pin "TP") (pinfunction "TP_TP") (pintype "input"))
      (node (ref "U$9") (pin "9") (pinfunction "REFP0_9") (pintype "bidirectional"))
    )
    (net (code "59") (name "RTS") (class "Default")
      (node (ref "Q1") (pin "4") (pinfunction "E_4") (pintype "passive"))
      (node (ref "R10") (pin "1") (pinfunction "1_1") (pintype "passive"))
      (node (ref "U1") (pin "2") (pinfunction "~{RTS}_2") (pintype "bidirectional"))
    )
    (net (code "60") (name "RXD") (class "Default")
      (node (ref "R13") (pin "2") (pinfunction "2_2") (pintype "passive"))
      (node (ref "U1") (pin "4") (pinfunction "RXD_4") (pintype "bidirectional"))
    )
    (net (code "61") (name "SCL") (class "Default")
      (node (ref "J4") (pin "4") (pinfunction "4_4") (pintype "passive"))
      (node (ref "R3") (pin "1") (pinfunction "1_1") (pintype "passive"))
      (node (ref "U$19") (pin "2") (pinfunction "P27/SCL_2") (pintype "bidirectional"))
    )
    (net (code "62") (name "SCL1") (class "Default")
      (node (ref "J1") (pin "4") (pinfunction "4_4") (pintype "passive"))
      (node (ref "R18") (pin "1") (pinfunction "1_1") (pintype "passive"))
    )
    (net (code "63") (name "SCLK") (class "Default")
      (node (ref "U$19") (pin "Z2") (pinfunction "Z2/P113_Z2") (pintype "bidirectional"))
      (node (ref "U$9") (pin "1") (pinfunction "SCLK_1") (pintype "bidirectional"))
    )
    (net (code "64") (name "SDA") (class "Default")
      (node (ref "J4") (pin "3") (pinfunction "3_3") (pintype "passive"))
      (node (ref "R4") (pin "1") (pinfunction "1_1") (pintype "passive"))
      (node (ref "U$19") (pin "1") (pinfunction "P26/SDA_1") (pintype "bidirectional"))
    )
    (net (code "65") (name "SDA1") (class "Default")
      (node (ref "J1") (pin "3") (pinfunction "3_3") (pintype "passive"))
      (node (ref "R5") (pin "1") (pinfunction "1_1") (pintype "passive"))
    )
    (net (code "66") (name "TXD") (class "Default")
      (node (ref "R12") (pin "2") (pinfunction "2_2") (pintype "passive"))
      (node (ref "U1") (pin "20") (pinfunction "TXD_20") (pintype "bidirectional"))
    )
    (net (code "67") (name "U0RXD") (class "Default")
      (node (ref "R12") (pin "1") (pinfunction "1_1") (pintype "passive"))
    )
    (net (code "68") (name "U0TXD") (class "Default")
      (node (ref "R13") (pin "1") (pinfunction "1_1") (pintype "passive"))
    )
    (net (code "69") (name "VBAT") (class "Default")
      (node (ref "C65") (pin "1") (pinfunction "1_1") (pintype "passive"))
      (node (ref "JP6") (pin "2") (pinfunction "2_2") (pintype "passive"))
      (node (ref "Q2") (pin "3") (pinfunction "D_3") (pintype "passive"))
      (node (ref "Q3") (pin "2") (pinfunction "S_2") (pintype "passive"))
      (node (ref "R27") (pin "2") (pinfunction "2_2") (pintype "passive"))
      (node (ref "R7") (pin "2") (pinfunction "2_2") (pintype "passive"))
      (node (ref "U3") (pin "3") (pinfunction "VBAT_3") (pintype "power_in"))
    )
    (net (code "70") (name "VCC") (class "Default")
      (node (ref "C44") (pin "1") (pinfunction "1_1") (pintype "passive"))
      (node (ref "C83") (pin "1") (pinfunction "1_1") (pintype "passive"))
      (node (ref "R20") (pin "1") (pinfunction "1_1") (pintype "passive"))
      (node (ref "TP41") (pin "TP") (pinfunction "TP_TP") (pintype "input"))
      (node (ref "U$13") (pin "4") (pinfunction "VOUT_4") (pintype "bidirectional"))
      (node (ref "U$15") (pin "5") (pinfunction "EN_5") (pintype "bidirectional"))
      (node (ref "U$15") (pin "8") (pinfunction "IN_8") (pintype "bidirectional"))
    )
    (net (code "71") (name "VIN") (class "Default")
      (node (ref "C1") (pin "1") (pinfunction "1_1") (pintype "passive"))
      (node (ref "C63") (pin "1") (pinfunction "1_1") (pintype "passive"))
      (node (ref "C72") (pin "2") (pinfunction "2_2") (pintype "passive"))
      (node (ref "D1") (pin "C") (pinfunction "C_C") (pintype "passive"))
      (node (ref "Q2") (pin "2") (pinfunction "S_2") (pintype "passive"))
      (node (ref "S2") (pin "3") (pinfunction "S_3") (pintype "passive"))
      (node (ref "U$1") (pin "P$1") (pinfunction "1_P$1") (pintype "passive"))
      (node (ref "U$13") (pin "1") (pinfunction "VIN_1") (pintype "bidirectional"))
      (node (ref "U8") (pin "1") (pinfunction "IN_1") (pintype "input"))
    )
    (net (code "72") (name "VUSB") (class "Default")
      (node (ref "C60") (pin "1") (pinfunction "1_1") (pintype "passive"))
      (node (ref "C61") (pin "1") (pinfunction "1_1") (pintype "passive"))
      (node (ref "C64") (pin "1") (pinfunction "1_1") (pintype "passive"))
      (node (ref "D1") (pin "A") (pinfunction "A_A") (pintype "passive"))
      (node (ref "JP7") (pin "1") (pinfunction "VCC_1") (pintype "bidirectional"))
      (node (ref "Q2") (pin "1") (pinfunction "G_1") (pintype "passive"))
      (node (ref "R16") (pin "1") (pinfunction "1_1") (pintype "passive"))
      (node (ref "R23") (pin "2") (pinfunction "2_2") (pintype "passive"))
      (node (ref "U1") (pin "15") (pinfunction "VCC_15") (pintype "bidirectional"))
      (node (ref "U3") (pin "4") (pinfunction "VIN_4") (pintype "power_in"))
    )
    (net (code "73") (name "WS2812") (class "Default")
      (node (ref "R6") (pin "2") (pinfunction "2_2") (pintype "passive"))
    )
    (net (code "74") (name "unconnected-(C8-Pad1)") (class "Default")
      (node (ref "C8") (pin "1") (pinfunction "1_1") (pintype "passive"))
    )
    (net (code "75") (name "unconnected-(JP7-ID-Pad4)") (class "Default")
      (node (ref "JP7") (pin "4") (pinfunction "ID_4") (pintype "bidirectional"))
    )
    (net (code "76") (name "unconnected-(LED1-DO-Pad2-DOUT)") (class "Default")
      (node (ref "LED1") (pin "2-DOUT") (pinfunction "DO_2-DOUT") (pintype "output"))
    )
    (net (code "77") (name "unconnected-(R22-Pad2)") (class "Default")
      (node (ref "R22") (pin "2") (pinfunction "2_2") (pintype "passive"))
    )
    (net (code "78") (name "unconnected-(R28-Pad2)") (class "Default")
      (node (ref "R28") (pin "2") (pinfunction "2_2") (pintype "passive"))
    )
    (net (code "79") (name "unconnected-(R29-Pad2)") (class "Default")
      (node (ref "R29") (pin "2") (pinfunction "2_2") (pintype "passive"))
    )
    (net (code "80") (name "unconnected-(SV2-Pad4)") (class "Default")
      (node (ref "SV2") (pin "4") (pinfunction "4_4") (pintype "passive"))
    )
    (net (code "81") (name "unconnected-(SV2-Pad5)") (class "Default")
      (node (ref "SV2") (pin "5") (pinfunction "5_5") (pintype "passive"))
    )
    (net (code "82") (name "unconnected-(SV4-Pad2)") (class "Default")
      (node (ref "SV4") (pin "2") (pinfunction "2_2") (pintype "passive"))
    )
    (net (code "83") (name "unconnected-(SV4-Pad3)") (class "Default")
      (node (ref "SV4") (pin "3") (pinfunction "3_3") (pintype "passive"))
    )
    (net (code "84") (name "unconnected-(SV4-Pad4)") (class "Default")
      (node (ref "SV4") (pin "4") (pinfunction "4_4") (pintype "passive"))
    )
    (net (code "85") (name "unconnected-(SV4-Pad5)") (class "Default")
      (node (ref "SV4") (pin "5") (pinfunction "5_5") (pintype "passive"))
    )
    (net (code "86") (name "unconnected-(SW2-P1-PadA')") (class "Default")
      (node (ref "SW2") (pin "A'") (pinfunction "P1_A'") (pintype "passive"))
    )
    (net (code "87") (name "unconnected-(U$19-A0{slash}VSS1-PadA0)") (class "Default")
      (node (ref "U$19") (pin "A0") (pinfunction "A0/VSS1_A0") (pintype "bidirectional"))
    )
    (net (code "88") (name "unconnected-(U$19-A1{slash}P28-PadA1)") (class "Default")
      (node (ref "U$19") (pin "A1") (pinfunction "A1/P28_A1") (pintype "bidirectional"))
    )
    (net (code "89") (name "unconnected-(U$19-A2{slash}P29-PadA2)") (class "Default")
      (node (ref "U$19") (pin "A2") (pinfunction "A2/P29_A2") (pintype "bidirectional"))
    )
    (net (code "90") (name "unconnected-(U$19-A3{slash}P04-PadA3)") (class "Default")
      (node (ref "U$19") (pin "A3") (pinfunction "A3/P04_A3") (pintype "bidirectional"))
    )
    (net (code "91") (name "unconnected-(U$19-A4{slash}P05-PadA4)") (class "Default")
      (node (ref "U$19") (pin "A4") (pinfunction "A4/P05_A4") (pintype "bidirectional"))
    )
    (net (code "92") (name "unconnected-(U$19-A5{slash}P07-PadA5)") (class "Default")
      (node (ref "U$19") (pin "A5") (pinfunction "A5/P07_A5") (pintype "bidirectional"))
    )
    (net (code "93") (name "unconnected-(U$19-A6{slash}P108-PadA6)") (class "Default")
      (node (ref "U$19") (pin "A6") (pinfunction "A6/P108_A6") (pintype "bidirectional"))
    )
    (net (code "94") (name "unconnected-(U$19-B0{slash}VSS2-PadB0)") (class "Default")
      (node (ref "U$19") (pin "B0") (pinfunction "B0/VSS2_B0") (pintype "bidirectional"))
    )
    (net (code "95") (name "unconnected-(U$19-B1{slash}P25-PadB1)") (class "Default")
      (node (ref "U$19") (pin "B1") (pinfunction "B1/P25_B1") (pintype "bidirectional"))
    )
    (net (code "96") (name "unconnected-(U$19-B2{slash}P30-PadB2)") (class "Default")
      (node (ref "U$19") (pin "B2") (pinfunction "B2/P30_B2") (pintype "bidirectional"))
    )
    (net (code "97") (name "unconnected-(U$19-B3{slash}P31-PadB3)") (class "Default")
      (node (ref "U$19") (pin "B3") (pinfunction "B3/P31_B3") (pintype "bidirectional"))
    )
    (net (code "98") (name "unconnected-(U$19-B4{slash}NC-PadB4)") (class "Default")
      (node (ref "U$19") (pin "B4") (pinfunction "B4/NC_B4") (pintype "bidirectional"))
    )
    (net (code "99") (name "unconnected-(U$19-B5{slash}P08-PadB5)") (class "Default")
      (node (ref "U$19") (pin "B5") (pinfunction "B5/P08_B5") (pintype "bidirectional"))
    )
    (net (code "100") (name "unconnected-(U$19-B6{slash}P103-PadB6)") (class "Default")
      (node (ref "U$19") (pin "B6") (pinfunction "B6/P103_B6") (pintype "bidirectional"))
    )
    (net (code "101") (name "unconnected-(U$19-C0{slash}VSS3-PadC0)") (class "Default")
      (node (ref "U$19") (pin "C0") (pinfunction "C0/VSS3_C0") (pintype "bidirectional"))
    )
    (net (code "102") (name "unconnected-(U$19-C1{slash}P24-PadC1)") (class "Default")
      (node (ref "U$19") (pin "C1") (pinfunction "C1/P24_C1") (pintype "bidirectional"))
    )
    (net (code "103") (name "unconnected-(U$19-C4{slash}P15-PadC4)") (class "Default")
      (node (ref "U$19") (pin "C4") (pinfunction "C4/P15_C4") (pintype "bidirectional"))
    )
    (net (code "104") (name "unconnected-(U$19-C5{slash}P12-PadC5)") (class "Default")
      (node (ref "U$19") (pin "C5") (pinfunction "C5/P12_C5") (pintype "bidirectional"))
    )
    (net (code "105") (name "unconnected-(U$19-C6{slash}P104-PadC6)") (class "Default")
      (node (ref "U$19") (pin "C6") (pinfunction "C6/P104_C6") (pintype "bidirectional"))
    )
    (net (code "106") (name "unconnected-(U$19-D0{slash}VSS4-PadD0)") (class "Default")
      (node (ref "U$19") (pin "D0") (pinfunction "D0/VSS4_D0") (pintype "bidirectional"))
    )
    (net (code "107") (name "unconnected-(U$19-D3{slash}P16-PadD3)") (class "Default")
      (node (ref "U$19") (pin "D3") (pinfunction "D3/P16_D3") (pintype "bidirectional"))
    )
    (net (code "108") (name "unconnected-(U$19-D4{slash}P14-PadD4)") (class "Default")
      (node (ref "U$19") (pin "D4") (pinfunction "D4/P14_D4") (pintype "bidirectional"))
    )
    (net (code "109") (name "unconnected-(U$19-D5{slash}P11-PadD5)") (class "Default")
      (node (ref "U$19") (pin "D5") (pinfunction "D5/P11_D5") (pintype "bidirectional"))
    )
    (net (code "110") (name "unconnected-(U$19-D6{slash}P105-PadD6)") (class "Default")
      (node (ref "U$19") (pin "D6") (pinfunction "D6/P105_D6") (pintype "bidirectional"))
    )
    (net (code "111") (name "unconnected-(U$19-E0{slash}P107-PadE0)") (class "Default")
      (node (ref "U$19") (pin "E0") (pinfunction "E0/P107_E0") (pintype "bidirectional"))
    )
    (net (code "112") (name "unconnected-(U$19-E1{slash}P20-PadE1)") (class "Default")
      (node (ref "U$19") (pin "E1") (pinfunction "E1/P20_E1") (pintype "bidirectional"))
    )
    (net (code "113") (name "unconnected-(U$19-E3{slash}P109-PadE3)") (class "Default")
      (node (ref "U$19") (pin "E3") (pinfunction "E3/P109_E3") (pintype "bidirectional"))
    )
    (net (code "114") (name "unconnected-(U$19-E4{slash}D+-PadE4)") (class "Default")
      (node (ref "U$19") (pin "E4") (pinfunction "E4/D+_E4") (pintype "bidirectional"))
    )
    (net (code "115") (name "unconnected-(U$19-E5{slash}D--PadE5)") (class "Default")
      (node (ref "U$19") (pin "E5") (pinfunction "E5/D-_E5") (pintype "bidirectional"))
    )
    (net (code "116") (name "unconnected-(U$19-E6{slash}P12-PadE6)") (class "Default")
      (node (ref "U$19") (pin "E6") (pinfunction "E6/P12_E6") (pintype "bidirectional"))
    )
    (net (code "117") (name "unconnected-(U$19-F0{slash}GND-PadP$17)") (class "Default")
      (node (ref "U$19") (pin "P$17") (pinfunction "F0/GND_P$17") (pintype "bidirectional"))
    )
    (net (code "118") (name "unconnected-(U$19-F1{slash}GND-PadP$18)") (class "Default")
      (node (ref "U$19") (pin "P$18") (pinfunction "F1/GND_P$18") (pintype "bidirectional"))
    )
    (net (code "119") (name "unconnected-(U$19-F2{slash}GND-PadP$19)") (class "Default")
      (node (ref "U$19") (pin "P$19") (pinfunction "F2/GND_P$19") (pintype "bidirectional"))
    )
    (net (code "120") (name "unconnected-(U$19-F3{slash}GND-PadP$20)") (class "Default")
      (node (ref "U$19") (pin "P$20") (pinfunction "F3/GND_P$20") (pintype "bidirectional"))
    )
    (net (code "121") (name "unconnected-(U$19-F4{slash}VDDH-PadF4)") (class "Default")
      (node (ref "U$19") (pin "F4") (pinfunction "F4/VDDH_F4") (pintype "bidirectional"))
    )
    (net (code "122") (name "unconnected-(U$19-F5{slash}DCCH-PadF5)") (class "Default")
      (node (ref "U$19") (pin "F5") (pinfunction "F5/DCCH_F5") (pintype "bidirectional"))
    )
    (net (code "123") (name "unconnected-(U$19-F6{slash}VBUS-PadF6)") (class "Default")
      (node (ref "U$19") (pin "F6") (pinfunction "F6/VBUS_F6") (pintype "bidirectional"))
    )
    (net (code "124") (name "unconnected-(U$19-P03{slash}AIN1-Pad6)") (class "Default")
      (node (ref "U$19") (pin "6") (pinfunction "P03/AIN1_6") (pintype "bidirectional"))
    )
    (net (code "125") (name "unconnected-(U$19-P09-Pad7)") (class "Default")
      (node (ref "U$19") (pin "7") (pinfunction "P09_7") (pintype "bidirectional"))
    )
    (net (code "126") (name "unconnected-(U$19-P10-Pad8)") (class "Default")
      (node (ref "U$19") (pin "8") (pinfunction "P10_8") (pintype "bidirectional"))
    )
    (net (code "127") (name "unconnected-(U1-CBUS0-Pad18)") (class "Default")
      (node (ref "U1") (pin "18") (pinfunction "CBUS0_18") (pintype "bidirectional"))
    )
    (net (code "128") (name "unconnected-(U1-CBUS1-Pad17)") (class "Default")
      (node (ref "U1") (pin "17") (pinfunction "CBUS1_17") (pintype "bidirectional"))
    )
    (net (code "129") (name "unconnected-(U1-CBUS2-Pad10)") (class "Default")
      (node (ref "U1") (pin "10") (pinfunction "CBUS2_10") (pintype "bidirectional"))
    )
    (net (code "130") (name "unconnected-(U1-CBUS3-Pad19)") (class "Default")
      (node (ref "U1") (pin "19") (pinfunction "CBUS3_19") (pintype "bidirectional"))
    )
    (net (code "131") (name "unconnected-(U1-~{CTS}-Pad9)") (class "Default")
      (node (ref "U1") (pin "9") (pinfunction "~{CTS}_9") (pintype "bidirectional"))
    )
    (net (code "132") (name "unconnected-(U1-~{DCD}-Pad8)") (class "Default")
      (node (ref "U1") (pin "8") (pinfunction "~{DCD}_8") (pintype "bidirectional"))
    )
    (net (code "133") (name "unconnected-(U1-~{DSR}-Pad7)") (class "Default")
      (node (ref "U1") (pin "7") (pinfunction "~{DSR}_7") (pintype "bidirectional"))
    )
    (net (code "134") (name "unconnected-(U1-~{RI}-Pad5)") (class "Default")
      (node (ref "U1") (pin "5") (pinfunction "~{RI}_5") (pintype "bidirectional"))
    )
    (net (code "135") (name "unconnected-(U8-BP-Pad4)") (class "Default")
      (node (ref "U8") (pin "4") (pinfunction "BP_4") (pintype "input"))
    )
    (net (code "136") (name "~{CS1}") (class "Default")
      (node (ref "R29") (pin "1") (pinfunction "1_1") (pintype "passive"))
      (node (ref "U$9") (pin "2") (pinfunction "~{CS}_2") (pintype "bidirectional"))
    )
    (net (code "137") (name "~{DRDY}") (class "Default")
      (node (ref "U$9") (pin "14") (pinfunction "~{DRDY}_14") (pintype "bidirectional"))
    )
  )
)
